# Wafer_Schematic.net
KiCad netlist of a schematic drawn in Altium Designer
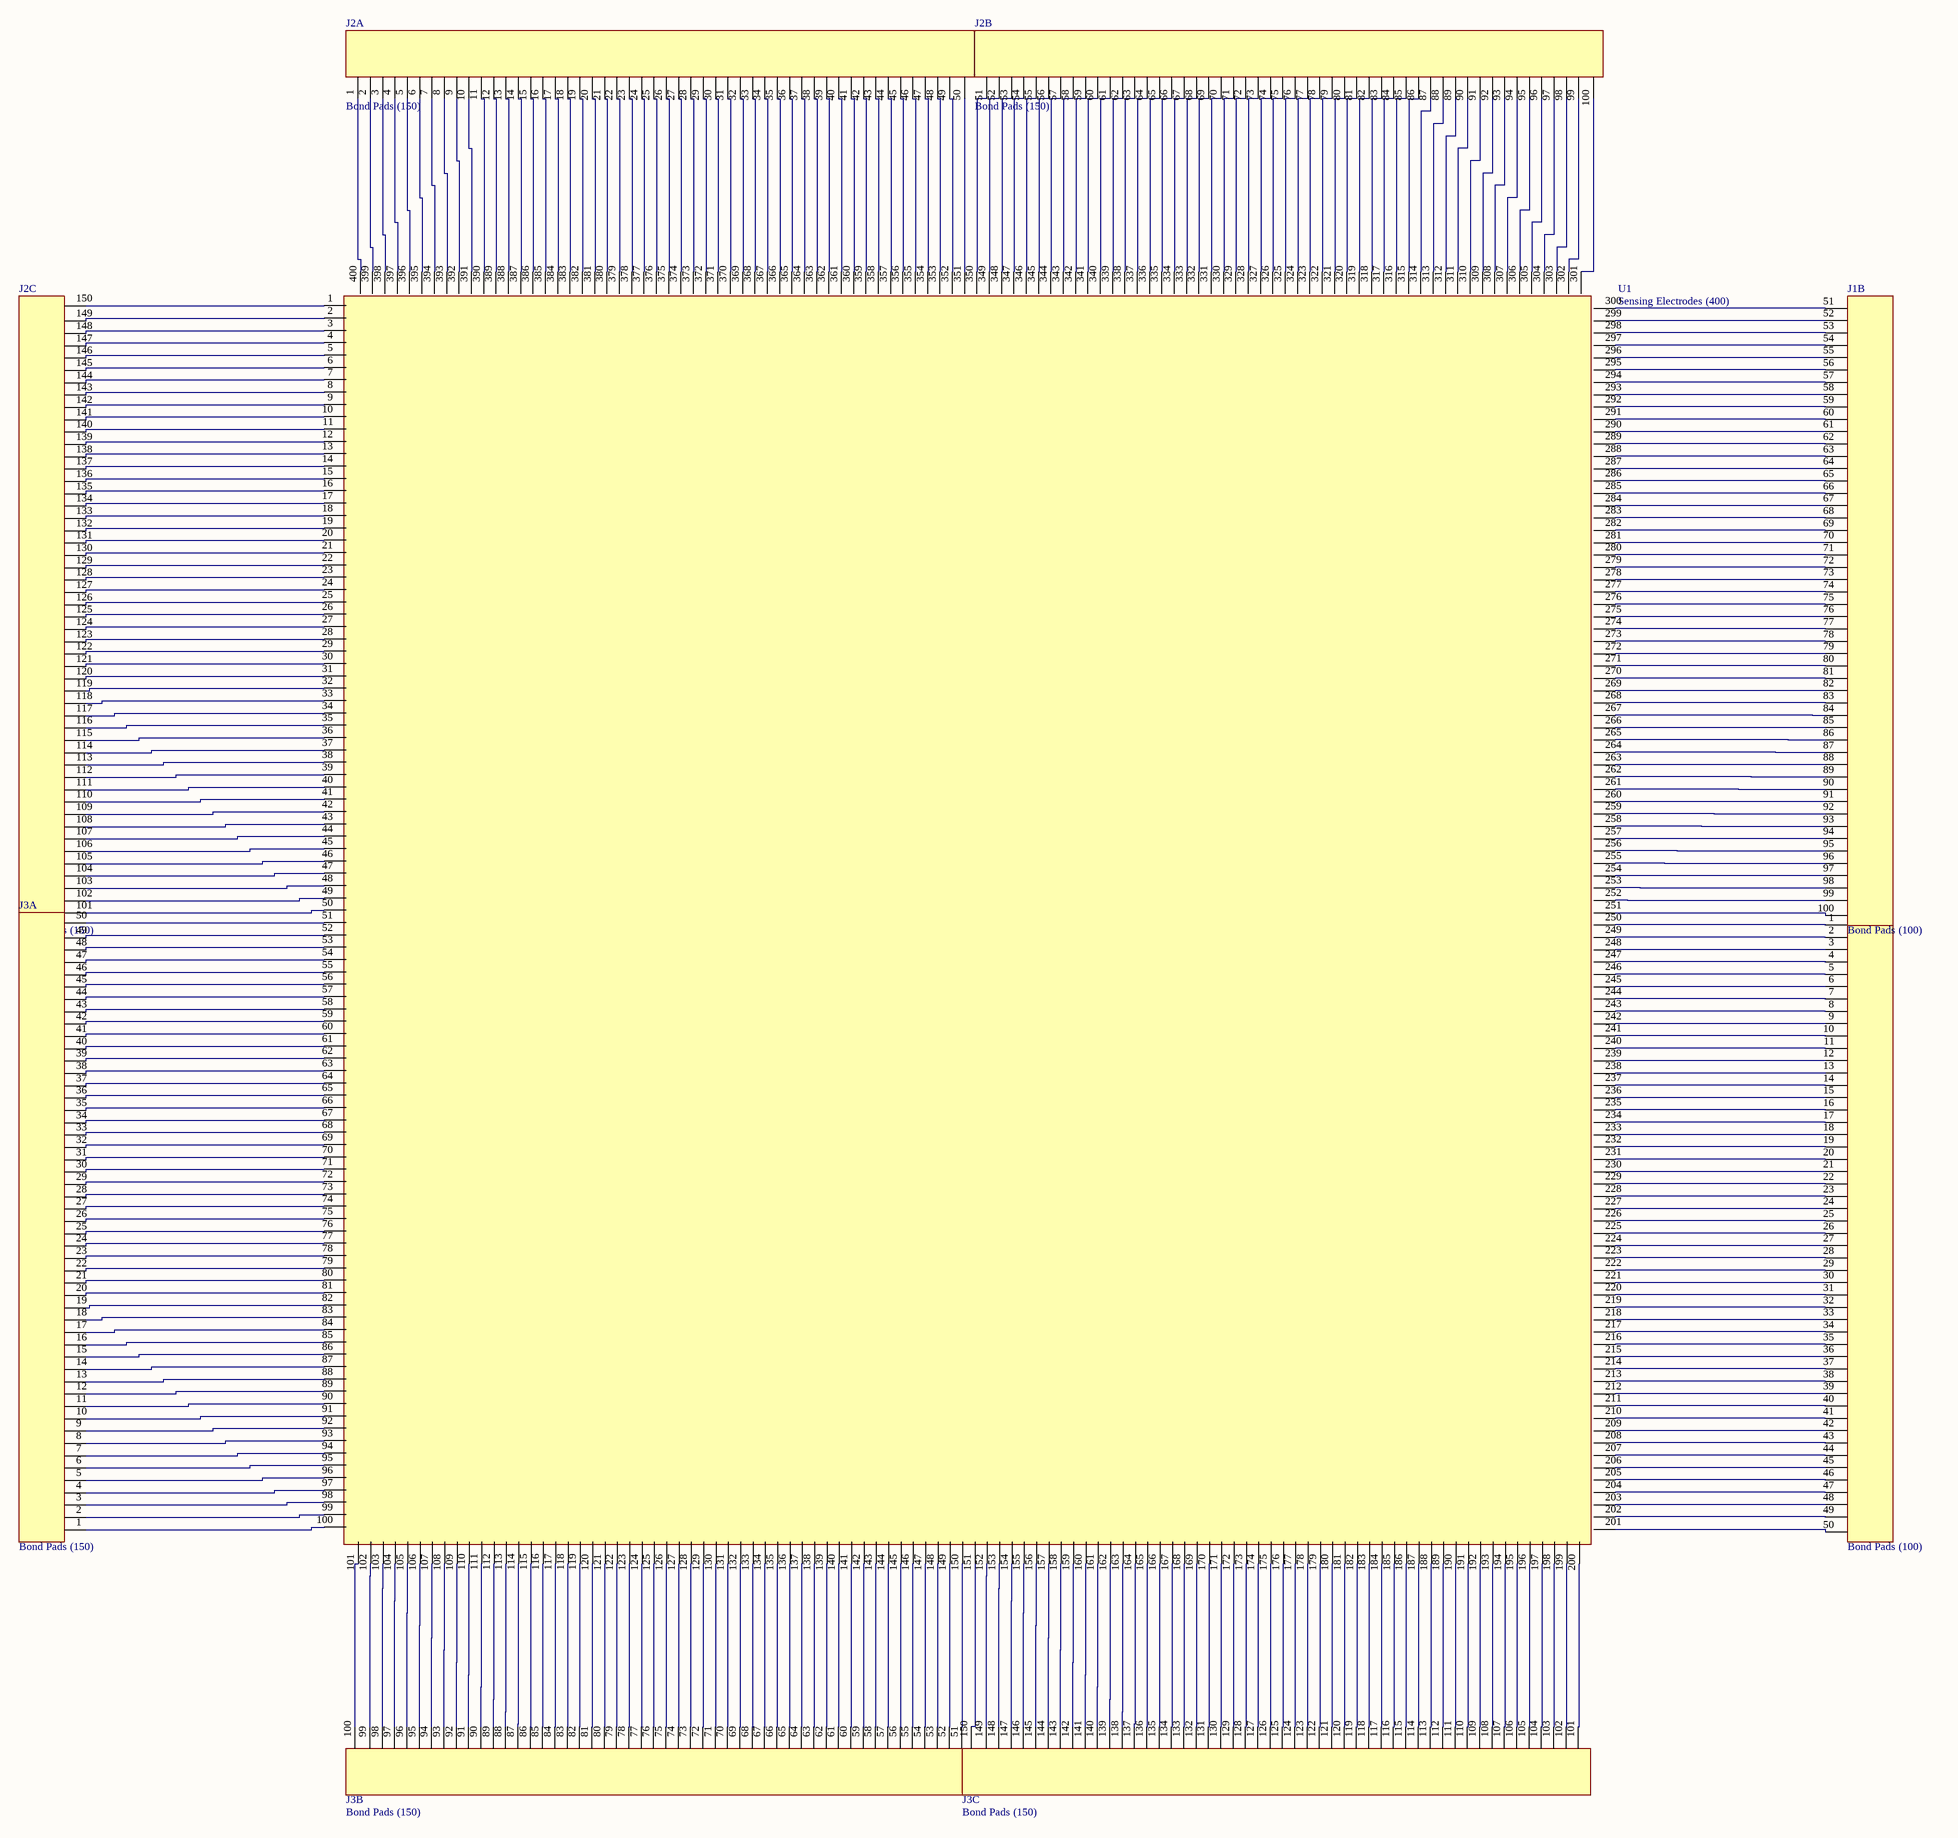
[diagram p0: Wafer Schematic.SchDoc]

(export (version "E")
  (design (tool "Eeschema 10.0.6"))
  (components
    (comp (ref "J1")
      (value "Bond Pads (100)")
      (footprint "BOND PADS (100)")
      (description "100 pads for the shorter side of the chip")
      (libsource (lib "Celestial Library Database") (part "Bond Pads (100)"))
    )
    (comp (ref "J2")
      (value "Bond Pads (150)")
      (footprint "BOND PADS (150)")
      (description "150 pads for the longer side of the chip")
      (libsource (lib "") (part "Bond Pads (150)_1"))
    )
    (comp (ref "J3")
      (value "Bond Pads (150)")
      (footprint "BOND PADS (150)")
      (description "150 pads for the longer side of the chip")
      (libsource (lib "Celestial Library Database") (part "Bond Pads (150)"))
    )
    (comp (ref "U1")
      (value "Sensing Electrodes (400)")
      (footprint "LGA400C100P20X20_2000X2000X0")
      (description "400 Electrodes covering a 2 mm by 2 mm sensing 10x")
      (fields (field (name "PART NUMBER") "Silicon Die Holder 400 Electrodes"))
      (libsource (lib "Celestial Library Database") (part "Sensing Electrodes (400)"))
    )
  )
  (nets
    (net (code "1") (name "Net-(J1-Pad1)") (class "Default")
      (node (ref "J1") (pin "1") (pintype "passive"))
      (node (ref "U1") (pin "250") (pintype "passive"))
    )
    (net (code "2") (name "Net-(J1-Pad2)") (class "Default")
      (node (ref "J1") (pin "2") (pintype "passive"))
      (node (ref "U1") (pin "249") (pintype "passive"))
    )
    (net (code "3") (name "Net-(J1-Pad3)") (class "Default")
      (node (ref "J1") (pin "3") (pintype "passive"))
      (node (ref "U1") (pin "248") (pintype "passive"))
    )
    (net (code "4") (name "Net-(J1-Pad4)") (class "Default")
      (node (ref "J1") (pin "4") (pintype "passive"))
      (node (ref "U1") (pin "247") (pintype "passive"))
    )
    (net (code "5") (name "Net-(J1-Pad5)") (class "Default")
      (node (ref "J1") (pin "5") (pintype "passive"))
      (node (ref "U1") (pin "246") (pintype "passive"))
    )
    (net (code "6") (name "Net-(J1-Pad6)") (class "Default")
      (node (ref "J1") (pin "6") (pintype "passive"))
      (node (ref "U1") (pin "245") (pintype "passive"))
    )
    (net (code "7") (name "Net-(J1-Pad7)") (class "Default")
      (node (ref "J1") (pin "7") (pintype "passive"))
      (node (ref "U1") (pin "244") (pintype "passive"))
    )
    (net (code "8") (name "Net-(J1-Pad8)") (class "Default")
      (node (ref "J1") (pin "8") (pintype "passive"))
      (node (ref "U1") (pin "243") (pintype "passive"))
    )
    (net (code "9") (name "Net-(J1-Pad9)") (class "Default")
      (node (ref "J1") (pin "9") (pintype "passive"))
      (node (ref "U1") (pin "242") (pintype "passive"))
    )
    (net (code "10") (name "Net-(J1-Pad10)") (class "Default")
      (node (ref "J1") (pin "10") (pintype "passive"))
      (node (ref "U1") (pin "241") (pintype "passive"))
    )
    (net (code "11") (name "Net-(J1-Pad11)") (class "Default")
      (node (ref "J1") (pin "11") (pintype "passive"))
      (node (ref "U1") (pin "240") (pintype "passive"))
    )
    (net (code "12") (name "Net-(J1-Pad12)") (class "Default")
      (node (ref "J1") (pin "12") (pintype "passive"))
      (node (ref "U1") (pin "239") (pintype "passive"))
    )
    (net (code "13") (name "Net-(J1-Pad13)") (class "Default")
      (node (ref "J1") (pin "13") (pintype "passive"))
      (node (ref "U1") (pin "238") (pintype "passive"))
    )
    (net (code "14") (name "Net-(J1-Pad14)") (class "Default")
      (node (ref "J1") (pin "14") (pintype "passive"))
      (node (ref "U1") (pin "237") (pintype "passive"))
    )
    (net (code "15") (name "Net-(J1-Pad15)") (class "Default")
      (node (ref "J1") (pin "15") (pintype "passive"))
      (node (ref "U1") (pin "236") (pintype "passive"))
    )
    (net (code "16") (name "Net-(J1-Pad16)") (class "Default")
      (node (ref "J1") (pin "16") (pintype "passive"))
      (node (ref "U1") (pin "235") (pintype "passive"))
    )
    (net (code "17") (name "Net-(J1-Pad17)") (class "Default")
      (node (ref "J1") (pin "17") (pintype "passive"))
      (node (ref "U1") (pin "234") (pintype "passive"))
    )
    (net (code "18") (name "Net-(J1-Pad18)") (class "Default")
      (node (ref "J1") (pin "18") (pintype "passive"))
      (node (ref "U1") (pin "233") (pintype "passive"))
    )
    (net (code "19") (name "Net-(J1-Pad19)") (class "Default")
      (node (ref "J1") (pin "19") (pintype "passive"))
      (node (ref "U1") (pin "232") (pintype "passive"))
    )
    (net (code "20") (name "Net-(J1-Pad20)") (class "Default")
      (node (ref "J1") (pin "20") (pintype "passive"))
      (node (ref "U1") (pin "231") (pintype "passive"))
    )
    (net (code "21") (name "Net-(J1-Pad21)") (class "Default")
      (node (ref "J1") (pin "21") (pintype "passive"))
      (node (ref "U1") (pin "230") (pintype "passive"))
    )
    (net (code "22") (name "Net-(J1-Pad22)") (class "Default")
      (node (ref "J1") (pin "22") (pintype "passive"))
      (node (ref "U1") (pin "229") (pintype "passive"))
    )
    (net (code "23") (name "Net-(J1-Pad23)") (class "Default")
      (node (ref "J1") (pin "23") (pintype "passive"))
      (node (ref "U1") (pin "228") (pintype "passive"))
    )
    (net (code "24") (name "Net-(J1-Pad24)") (class "Default")
      (node (ref "J1") (pin "24") (pintype "passive"))
      (node (ref "U1") (pin "227") (pintype "passive"))
    )
    (net (code "25") (name "Net-(J1-Pad25)") (class "Default")
      (node (ref "J1") (pin "25") (pintype "passive"))
      (node (ref "U1") (pin "226") (pintype "passive"))
    )
    (net (code "26") (name "Net-(J1-Pad26)") (class "Default")
      (node (ref "J1") (pin "26") (pintype "passive"))
      (node (ref "U1") (pin "225") (pintype "passive"))
    )
    (net (code "27") (name "Net-(J1-Pad27)") (class "Default")
      (node (ref "J1") (pin "27") (pintype "passive"))
      (node (ref "U1") (pin "224") (pintype "passive"))
    )
    (net (code "28") (name "Net-(J1-Pad28)") (class "Default")
      (node (ref "J1") (pin "28") (pintype "passive"))
      (node (ref "U1") (pin "223") (pintype "passive"))
    )
    (net (code "29") (name "Net-(J1-Pad29)") (class "Default")
      (node (ref "J1") (pin "29") (pintype "passive"))
      (node (ref "U1") (pin "222") (pintype "passive"))
    )
    (net (code "30") (name "Net-(J1-Pad30)") (class "Default")
      (node (ref "J1") (pin "30") (pintype "passive"))
      (node (ref "U1") (pin "221") (pintype "passive"))
    )
    (net (code "31") (name "Net-(J1-Pad31)") (class "Default")
      (node (ref "J1") (pin "31") (pintype "passive"))
      (node (ref "U1") (pin "220") (pintype "passive"))
    )
    (net (code "32") (name "Net-(J1-Pad32)") (class "Default")
      (node (ref "J1") (pin "32") (pintype "passive"))
      (node (ref "U1") (pin "219") (pintype "passive"))
    )
    (net (code "33") (name "Net-(J1-Pad33)") (class "Default")
      (node (ref "J1") (pin "33") (pintype "passive"))
      (node (ref "U1") (pin "218") (pintype "passive"))
    )
    (net (code "34") (name "Net-(J1-Pad34)") (class "Default")
      (node (ref "J1") (pin "34") (pintype "passive"))
      (node (ref "U1") (pin "217") (pintype "passive"))
    )
    (net (code "35") (name "Net-(J1-Pad35)") (class "Default")
      (node (ref "J1") (pin "35") (pintype "passive"))
      (node (ref "U1") (pin "216") (pintype "passive"))
    )
    (net (code "36") (name "Net-(J1-Pad36)") (class "Default")
      (node (ref "J1") (pin "36") (pintype "passive"))
      (node (ref "U1") (pin "215") (pintype "passive"))
    )
    (net (code "37") (name "Net-(J1-Pad37)") (class "Default")
      (node (ref "J1") (pin "37") (pintype "passive"))
      (node (ref "U1") (pin "214") (pintype "passive"))
    )
    (net (code "38") (name "Net-(J1-Pad38)") (class "Default")
      (node (ref "J1") (pin "38") (pintype "passive"))
      (node (ref "U1") (pin "213") (pintype "passive"))
    )
    (net (code "39") (name "Net-(J1-Pad39)") (class "Default")
      (node (ref "J1") (pin "39") (pintype "passive"))
      (node (ref "U1") (pin "212") (pintype "passive"))
    )
    (net (code "40") (name "Net-(J1-Pad40)") (class "Default")
      (node (ref "J1") (pin "40") (pintype "passive"))
      (node (ref "U1") (pin "211") (pintype "passive"))
    )
    (net (code "41") (name "Net-(J1-Pad41)") (class "Default")
      (node (ref "J1") (pin "41") (pintype "passive"))
      (node (ref "U1") (pin "210") (pintype "passive"))
    )
    (net (code "42") (name "Net-(J1-Pad42)") (class "Default")
      (node (ref "J1") (pin "42") (pintype "passive"))
      (node (ref "U1") (pin "209") (pintype "passive"))
    )
    (net (code "43") (name "Net-(J1-Pad43)") (class "Default")
      (node (ref "J1") (pin "43") (pintype "passive"))
      (node (ref "U1") (pin "208") (pintype "passive"))
    )
    (net (code "44") (name "Net-(J1-Pad44)") (class "Default")
      (node (ref "J1") (pin "44") (pintype "passive"))
      (node (ref "U1") (pin "207") (pintype "passive"))
    )
    (net (code "45") (name "Net-(J1-Pad45)") (class "Default")
      (node (ref "J1") (pin "45") (pintype "passive"))
      (node (ref "U1") (pin "206") (pintype "passive"))
    )
    (net (code "46") (name "Net-(J1-Pad46)") (class "Default")
      (node (ref "J1") (pin "46") (pintype "passive"))
      (node (ref "U1") (pin "205") (pintype "passive"))
    )
    (net (code "47") (name "Net-(J1-Pad47)") (class "Default")
      (node (ref "J1") (pin "47") (pintype "passive"))
      (node (ref "U1") (pin "204") (pintype "passive"))
    )
    (net (code "48") (name "Net-(J1-Pad48)") (class "Default")
      (node (ref "J1") (pin "48") (pintype "passive"))
      (node (ref "U1") (pin "203") (pintype "passive"))
    )
    (net (code "49") (name "Net-(J1-Pad49)") (class "Default")
      (node (ref "J1") (pin "49") (pintype "passive"))
      (node (ref "U1") (pin "202") (pintype "passive"))
    )
    (net (code "50") (name "Net-(J1-Pad50)") (class "Default")
      (node (ref "J1") (pin "50") (pintype "passive"))
      (node (ref "U1") (pin "201") (pintype "passive"))
    )
    (net (code "51") (name "Net-(J1-Pad51)") (class "Default")
      (node (ref "J1") (pin "51") (pintype "passive"))
      (node (ref "U1") (pin "300") (pintype "passive"))
    )
    (net (code "52") (name "Net-(J1-Pad52)") (class "Default")
      (node (ref "J1") (pin "52") (pintype "passive"))
      (node (ref "U1") (pin "299") (pintype "passive"))
    )
    (net (code "53") (name "Net-(J1-Pad53)") (class "Default")
      (node (ref "J1") (pin "53") (pintype "passive"))
      (node (ref "U1") (pin "298") (pintype "passive"))
    )
    (net (code "54") (name "Net-(J1-Pad54)") (class "Default")
      (node (ref "J1") (pin "54") (pintype "passive"))
      (node (ref "U1") (pin "297") (pintype "passive"))
    )
    (net (code "55") (name "Net-(J1-Pad55)") (class "Default")
      (node (ref "J1") (pin "55") (pintype "passive"))
      (node (ref "U1") (pin "296") (pintype "passive"))
    )
    (net (code "56") (name "Net-(J1-Pad56)") (class "Default")
      (node (ref "J1") (pin "56") (pintype "passive"))
      (node (ref "U1") (pin "295") (pintype "passive"))
    )
    (net (code "57") (name "Net-(J1-Pad57)") (class "Default")
      (node (ref "J1") (pin "57") (pintype "passive"))
      (node (ref "U1") (pin "294") (pintype "passive"))
    )
    (net (code "58") (name "Net-(J1-Pad58)") (class "Default")
      (node (ref "J1") (pin "58") (pintype "passive"))
      (node (ref "U1") (pin "293") (pintype "passive"))
    )
    (net (code "59") (name "Net-(J1-Pad59)") (class "Default")
      (node (ref "J1") (pin "59") (pintype "passive"))
      (node (ref "U1") (pin "292") (pintype "passive"))
    )
    (net (code "60") (name "Net-(J1-Pad60)") (class "Default")
      (node (ref "J1") (pin "60") (pintype "passive"))
      (node (ref "U1") (pin "291") (pintype "passive"))
    )
    (net (code "61") (name "Net-(J1-Pad61)") (class "Default")
      (node (ref "J1") (pin "61") (pintype "passive"))
      (node (ref "U1") (pin "290") (pintype "passive"))
    )
    (net (code "62") (name "Net-(J1-Pad62)") (class "Default")
      (node (ref "J1") (pin "62") (pintype "passive"))
      (node (ref "U1") (pin "289") (pintype "passive"))
    )
    (net (code "63") (name "Net-(J1-Pad63)") (class "Default")
      (node (ref "J1") (pin "63") (pintype "passive"))
      (node (ref "U1") (pin "288") (pintype "passive"))
    )
    (net (code "64") (name "Net-(J1-Pad64)") (class "Default")
      (node (ref "J1") (pin "64") (pintype "passive"))
      (node (ref "U1") (pin "287") (pintype "passive"))
    )
    (net (code "65") (name "Net-(J1-Pad65)") (class "Default")
      (node (ref "J1") (pin "65") (pintype "passive"))
      (node (ref "U1") (pin "286") (pintype "passive"))
    )
    (net (code "66") (name "Net-(J1-Pad66)") (class "Default")
      (node (ref "J1") (pin "66") (pintype "passive"))
      (node (ref "U1") (pin "285") (pintype "passive"))
    )
    (net (code "67") (name "Net-(J1-Pad67)") (class "Default")
      (node (ref "J1") (pin "67") (pintype "passive"))
      (node (ref "U1") (pin "284") (pintype "passive"))
    )
    (net (code "68") (name "Net-(J1-Pad68)") (class "Default")
      (node (ref "J1") (pin "68") (pintype "passive"))
      (node (ref "U1") (pin "283") (pintype "passive"))
    )
    (net (code "69") (name "Net-(J1-Pad69)") (class "Default")
      (node (ref "J1") (pin "69") (pintype "passive"))
      (node (ref "U1") (pin "282") (pintype "passive"))
    )
    (net (code "70") (name "Net-(J1-Pad70)") (class "Default")
      (node (ref "J1") (pin "70") (pintype "passive"))
      (node (ref "U1") (pin "281") (pintype "passive"))
    )
    (net (code "71") (name "Net-(J1-Pad71)") (class "Default")
      (node (ref "J1") (pin "71") (pintype "passive"))
      (node (ref "U1") (pin "280") (pintype "passive"))
    )
    (net (code "72") (name "Net-(J1-Pad72)") (class "Default")
      (node (ref "J1") (pin "72") (pintype "passive"))
      (node (ref "U1") (pin "279") (pintype "passive"))
    )
    (net (code "73") (name "Net-(J1-Pad73)") (class "Default")
      (node (ref "J1") (pin "73") (pintype "passive"))
      (node (ref "U1") (pin "278") (pintype "passive"))
    )
    (net (code "74") (name "Net-(J1-Pad74)") (class "Default")
      (node (ref "J1") (pin "74") (pintype "passive"))
      (node (ref "U1") (pin "277") (pintype "passive"))
    )
    (net (code "75") (name "Net-(J1-Pad75)") (class "Default")
      (node (ref "J1") (pin "75") (pintype "passive"))
      (node (ref "U1") (pin "276") (pintype "passive"))
    )
    (net (code "76") (name "Net-(J1-Pad76)") (class "Default")
      (node (ref "J1") (pin "76") (pintype "passive"))
      (node (ref "U1") (pin "275") (pintype "passive"))
    )
    (net (code "77") (name "Net-(J1-Pad77)") (class "Default")
      (node (ref "J1") (pin "77") (pintype "passive"))
      (node (ref "U1") (pin "274") (pintype "passive"))
    )
    (net (code "78") (name "Net-(J1-Pad78)") (class "Default")
      (node (ref "J1") (pin "78") (pintype "passive"))
      (node (ref "U1") (pin "273") (pintype "passive"))
    )
    (net (code "79") (name "Net-(J1-Pad79)") (class "Default")
      (node (ref "J1") (pin "79") (pintype "passive"))
      (node (ref "U1") (pin "272") (pintype "passive"))
    )
    (net (code "80") (name "Net-(J1-Pad80)") (class "Default")
      (node (ref "J1") (pin "80") (pintype "passive"))
      (node (ref "U1") (pin "271") (pintype "passive"))
    )
    (net (code "81") (name "Net-(J1-Pad81)") (class "Default")
      (node (ref "J1") (pin "81") (pintype "passive"))
      (node (ref "U1") (pin "270") (pintype "passive"))
    )
    (net (code "82") (name "Net-(J1-Pad82)") (class "Default")
      (node (ref "J1") (pin "82") (pintype "passive"))
      (node (ref "U1") (pin "269") (pintype "passive"))
    )
    (net (code "83") (name "Net-(J1-Pad83)") (class "Default")
      (node (ref "J1") (pin "83") (pintype "passive"))
      (node (ref "U1") (pin "268") (pintype "passive"))
    )
    (net (code "84") (name "Net-(J1-Pad84)") (class "Default")
      (node (ref "J1") (pin "84") (pintype "passive"))
      (node (ref "U1") (pin "267") (pintype "passive"))
    )
    (net (code "85") (name "Net-(J1-Pad85)") (class "Default")
      (node (ref "J1") (pin "85") (pintype "passive"))
      (node (ref "U1") (pin "266") (pintype "passive"))
    )
    (net (code "86") (name "Net-(J1-Pad86)") (class "Default")
      (node (ref "J1") (pin "86") (pintype "passive"))
      (node (ref "U1") (pin "265") (pintype "passive"))
    )
    (net (code "87") (name "Net-(J1-Pad87)") (class "Default")
      (node (ref "J1") (pin "87") (pintype "passive"))
      (node (ref "U1") (pin "264") (pintype "passive"))
    )
    (net (code "88") (name "Net-(J1-Pad88)") (class "Default")
      (node (ref "J1") (pin "88") (pintype "passive"))
      (node (ref "U1") (pin "263") (pintype "passive"))
    )
    (net (code "89") (name "Net-(J1-Pad89)") (class "Default")
      (node (ref "J1") (pin "89") (pintype "passive"))
      (node (ref "U1") (pin "262") (pintype "passive"))
    )
    (net (code "90") (name "Net-(J1-Pad90)") (class "Default")
      (node (ref "J1") (pin "90") (pintype "passive"))
      (node (ref "U1") (pin "261") (pintype "passive"))
    )
    (net (code "91") (name "Net-(J1-Pad91)") (class "Default")
      (node (ref "J1") (pin "91") (pintype "passive"))
      (node (ref "U1") (pin "260") (pintype "passive"))
    )
    (net (code "92") (name "Net-(J1-Pad92)") (class "Default")
      (node (ref "J1") (pin "92") (pintype "passive"))
      (node (ref "U1") (pin "259") (pintype "passive"))
    )
    (net (code "93") (name "Net-(J1-Pad93)") (class "Default")
      (node (ref "J1") (pin "93") (pintype "passive"))
      (node (ref "U1") (pin "258") (pintype "passive"))
    )
    (net (code "94") (name "Net-(J1-Pad94)") (class "Default")
      (node (ref "J1") (pin "94") (pintype "passive"))
      (node (ref "U1") (pin "257") (pintype "passive"))
    )
    (net (code "95") (name "Net-(J1-Pad95)") (class "Default")
      (node (ref "J1") (pin "95") (pintype "passive"))
      (node (ref "U1") (pin "256") (pintype "passive"))
    )
    (net (code "96") (name "Net-(J1-Pad96)") (class "Default")
      (node (ref "J1") (pin "96") (pintype "passive"))
      (node (ref "U1") (pin "255") (pintype "passive"))
    )
    (net (code "97") (name "Net-(J1-Pad97)") (class "Default")
      (node (ref "J1") (pin "97") (pintype "passive"))
      (node (ref "U1") (pin "254") (pintype "passive"))
    )
    (net (code "98") (name "Net-(J1-Pad98)") (class "Default")
      (node (ref "J1") (pin "98") (pintype "passive"))
      (node (ref "U1") (pin "253") (pintype "passive"))
    )
    (net (code "99") (name "Net-(J1-Pad99)") (class "Default")
      (node (ref "J1") (pin "99") (pintype "passive"))
      (node (ref "U1") (pin "252") (pintype "passive"))
    )
    (net (code "100") (name "Net-(J1-Pad100)") (class "Default")
      (node (ref "J1") (pin "100") (pintype "passive"))
      (node (ref "U1") (pin "251") (pintype "passive"))
    )
    (net (code "101") (name "Net-(J2-Pad1)") (class "Default")
      (node (ref "J2") (pin "1") (pintype "passive"))
      (node (ref "U1") (pin "400") (pintype "passive"))
    )
    (net (code "102") (name "Net-(J2-Pad2)") (class "Default")
      (node (ref "J2") (pin "2") (pintype "passive"))
      (node (ref "U1") (pin "399") (pintype "passive"))
    )
    (net (code "103") (name "Net-(J2-Pad3)") (class "Default")
      (node (ref "J2") (pin "3") (pintype "passive"))
      (node (ref "U1") (pin "398") (pintype "passive"))
    )
    (net (code "104") (name "Net-(J2-Pad4)") (class "Default")
      (node (ref "J2") (pin "4") (pintype "passive"))
      (node (ref "U1") (pin "397") (pintype "passive"))
    )
    (net (code "105") (name "Net-(J2-Pad5)") (class "Default")
      (node (ref "J2") (pin "5") (pintype "passive"))
      (node (ref "U1") (pin "396") (pintype "passive"))
    )
    (net (code "106") (name "Net-(J2-Pad6)") (class "Default")
      (node (ref "J2") (pin "6") (pintype "passive"))
      (node (ref "U1") (pin "395") (pintype "passive"))
    )
    (net (code "107") (name "Net-(J2-Pad7)") (class "Default")
      (node (ref "J2") (pin "7") (pintype "passive"))
      (node (ref "U1") (pin "394") (pintype "passive"))
    )
    (net (code "108") (name "Net-(J2-Pad8)") (class "Default")
      (node (ref "J2") (pin "8") (pintype "passive"))
      (node (ref "U1") (pin "393") (pintype "passive"))
    )
    (net (code "109") (name "Net-(J2-Pad9)") (class "Default")
      (node (ref "J2") (pin "9") (pintype "passive"))
      (node (ref "U1") (pin "392") (pintype "passive"))
    )
    (net (code "110") (name "Net-(J2-Pad10)") (class "Default")
      (node (ref "J2") (pin "10") (pintype "passive"))
      (node (ref "U1") (pin "391") (pintype "passive"))
    )
    (net (code "111") (name "Net-(J2-Pad11)") (class "Default")
      (node (ref "J2") (pin "11") (pintype "passive"))
      (node (ref "U1") (pin "390") (pintype "passive"))
    )
    (net (code "112") (name "Net-(J2-Pad12)") (class "Default")
      (node (ref "J2") (pin "12") (pintype "passive"))
      (node (ref "U1") (pin "389") (pintype "passive"))
    )
    (net (code "113") (name "Net-(J2-Pad13)") (class "Default")
      (node (ref "J2") (pin "13") (pintype "passive"))
      (node (ref "U1") (pin "388") (pintype "passive"))
    )
    (net (code "114") (name "Net-(J2-Pad14)") (class "Default")
      (node (ref "J2") (pin "14") (pintype "passive"))
      (node (ref "U1") (pin "387") (pintype "passive"))
    )
    (net (code "115") (name "Net-(J2-Pad15)") (class "Default")
      (node (ref "J2") (pin "15") (pintype "passive"))
      (node (ref "U1") (pin "386") (pintype "passive"))
    )
    (net (code "116") (name "Net-(J2-Pad16)") (class "Default")
      (node (ref "J2") (pin "16") (pintype "passive"))
      (node (ref "U1") (pin "385") (pintype "passive"))
    )
    (net (code "117") (name "Net-(J2-Pad17)") (class "Default")
      (node (ref "J2") (pin "17") (pintype "passive"))
      (node (ref "U1") (pin "384") (pintype "passive"))
    )
    (net (code "118") (name "Net-(J2-Pad18)") (class "Default")
      (node (ref "J2") (pin "18") (pintype "passive"))
      (node (ref "U1") (pin "383") (pintype "passive"))
    )
    (net (code "119") (name "Net-(J2-Pad19)") (class "Default")
      (node (ref "J2") (pin "19") (pintype "passive"))
      (node (ref "U1") (pin "382") (pintype "passive"))
    )
    (net (code "120") (name "Net-(J2-Pad20)") (class "Default")
      (node (ref "J2") (pin "20") (pintype "passive"))
      (node (ref "U1") (pin "381") (pintype "passive"))
    )
    (net (code "121") (name "Net-(J2-Pad21)") (class "Default")
      (node (ref "J2") (pin "21") (pintype "passive"))
      (node (ref "U1") (pin "380") (pintype "passive"))
    )
    (net (code "122") (name "Net-(J2-Pad22)") (class "Default")
      (node (ref "J2") (pin "22") (pintype "passive"))
      (node (ref "U1") (pin "379") (pintype "passive"))
    )
    (net (code "123") (name "Net-(J2-Pad23)") (class "Default")
      (node (ref "J2") (pin "23") (pintype "passive"))
      (node (ref "U1") (pin "378") (pintype "passive"))
    )
    (net (code "124") (name "Net-(J2-Pad24)") (class "Default")
      (node (ref "J2") (pin "24") (pintype "passive"))
      (node (ref "U1") (pin "377") (pintype "passive"))
    )
    (net (code "125") (name "Net-(J2-Pad25)") (class "Default")
      (node (ref "J2") (pin "25") (pintype "passive"))
      (node (ref "U1") (pin "376") (pintype "passive"))
    )
    (net (code "126") (name "Net-(J2-Pad26)") (class "Default")
      (node (ref "J2") (pin "26") (pintype "passive"))
      (node (ref "U1") (pin "375") (pintype "passive"))
    )
    (net (code "127") (name "Net-(J2-Pad27)") (class "Default")
      (node (ref "J2") (pin "27") (pintype "passive"))
      (node (ref "U1") (pin "374") (pintype "passive"))
    )
    (net (code "128") (name "Net-(J2-Pad28)") (class "Default")
      (node (ref "J2") (pin "28") (pintype "passive"))
      (node (ref "U1") (pin "373") (pintype "passive"))
    )
    (net (code "129") (name "Net-(J2-Pad29)") (class "Default")
      (node (ref "J2") (pin "29") (pintype "passive"))
      (node (ref "U1") (pin "372") (pintype "passive"))
    )
    (net (code "130") (name "Net-(J2-Pad30)") (class "Default")
      (node (ref "J2") (pin "30") (pintype "passive"))
      (node (ref "U1") (pin "371") (pintype "passive"))
    )
    (net (code "131") (name "Net-(J2-Pad31)") (class "Default")
      (node (ref "J2") (pin "31") (pintype "passive"))
      (node (ref "U1") (pin "370") (pintype "passive"))
    )
    (net (code "132") (name "Net-(J2-Pad32)") (class "Default")
      (node (ref "J2") (pin "32") (pintype "passive"))
      (node (ref "U1") (pin "369") (pintype "passive"))
    )
    (net (code "133") (name "Net-(J2-Pad33)") (class "Default")
      (node (ref "J2") (pin "33") (pintype "passive"))
      (node (ref "U1") (pin "368") (pintype "passive"))
    )
    (net (code "134") (name "Net-(J2-Pad34)") (class "Default")
      (node (ref "J2") (pin "34") (pintype "passive"))
      (node (ref "U1") (pin "367") (pintype "passive"))
    )
    (net (code "135") (name "Net-(J2-Pad35)") (class "Default")
      (node (ref "J2") (pin "35") (pintype "passive"))
      (node (ref "U1") (pin "366") (pintype "passive"))
    )
    (net (code "136") (name "Net-(J2-Pad36)") (class "Default")
      (node (ref "J2") (pin "36") (pintype "passive"))
      (node (ref "U1") (pin "365") (pintype "passive"))
    )
    (net (code "137") (name "Net-(J2-Pad37)") (class "Default")
      (node (ref "J2") (pin "37") (pintype "passive"))
      (node (ref "U1") (pin "364") (pintype "passive"))
    )
    (net (code "138") (name "Net-(J2-Pad38)") (class "Default")
      (node (ref "J2") (pin "38") (pintype "passive"))
      (node (ref "U1") (pin "363") (pintype "passive"))
    )
    (net (code "139") (name "Net-(J2-Pad39)") (class "Default")
      (node (ref "J2") (pin "39") (pintype "passive"))
      (node (ref "U1") (pin "362") (pintype "passive"))
    )
    (net (code "140") (name "Net-(J2-Pad40)") (class "Default")
      (node (ref "J2") (pin "40") (pintype "passive"))
      (node (ref "U1") (pin "361") (pintype "passive"))
    )
    (net (code "141") (name "Net-(J2-Pad41)") (class "Default")
      (node (ref "J2") (pin "41") (pintype "passive"))
      (node (ref "U1") (pin "360") (pintype "passive"))
    )
    (net (code "142") (name "Net-(J2-Pad42)") (class "Default")
      (node (ref "J2") (pin "42") (pintype "passive"))
      (node (ref "U1") (pin "359") (pintype "passive"))
    )
    (net (code "143") (name "Net-(J2-Pad43)") (class "Default")
      (node (ref "J2") (pin "43") (pintype "passive"))
      (node (ref "U1") (pin "358") (pintype "passive"))
    )
    (net (code "144") (name "Net-(J2-Pad44)") (class "Default")
      (node (ref "J2") (pin "44") (pintype "passive"))
      (node (ref "U1") (pin "357") (pintype "passive"))
    )
    (net (code "145") (name "Net-(J2-Pad45)") (class "Default")
      (node (ref "J2") (pin "45") (pintype "passive"))
      (node (ref "U1") (pin "356") (pintype "passive"))
    )
    (net (code "146") (name "Net-(J2-Pad46)") (class "Default")
      (node (ref "J2") (pin "46") (pintype "passive"))
      (node (ref "U1") (pin "355") (pintype "passive"))
    )
    (net (code "147") (name "Net-(J2-Pad47)") (class "Default")
      (node (ref "J2") (pin "47") (pintype "passive"))
      (node (ref "U1") (pin "354") (pintype "passive"))
    )
    (net (code "148") (name "Net-(J2-Pad48)") (class "Default")
      (node (ref "J2") (pin "48") (pintype "passive"))
      (node (ref "U1") (pin "353") (pintype "passive"))
    )
    (net (code "149") (name "Net-(J2-Pad49)") (class "Default")
      (node (ref "J2") (pin "49") (pintype "passive"))
      (node (ref "U1") (pin "352") (pintype "passive"))
    )
    (net (code "150") (name "Net-(J2-Pad50)") (class "Default")
      (node (ref "J2") (pin "50") (pintype "passive"))
      (node (ref "U1") (pin "351") (pintype "passive"))
    )
    (net (code "151") (name "Net-(J2-Pad51)") (class "Default")
      (node (ref "J2") (pin "51") (pintype "passive"))
      (node (ref "U1") (pin "350") (pintype "passive"))
    )
    (net (code "152") (name "Net-(J2-Pad52)") (class "Default")
      (node (ref "J2") (pin "52") (pintype "passive"))
      (node (ref "U1") (pin "349") (pintype "passive"))
    )
    (net (code "153") (name "Net-(J2-Pad53)") (class "Default")
      (node (ref "J2") (pin "53") (pintype "passive"))
      (node (ref "U1") (pin "348") (pintype "passive"))
    )
    (net (code "154") (name "Net-(J2-Pad54)") (class "Default")
      (node (ref "J2") (pin "54") (pintype "passive"))
      (node (ref "U1") (pin "347") (pintype "passive"))
    )
    (net (code "155") (name "Net-(J2-Pad55)") (class "Default")
      (node (ref "J2") (pin "55") (pintype "passive"))
      (node (ref "U1") (pin "346") (pintype "passive"))
    )
    (net (code "156") (name "Net-(J2-Pad56)") (class "Default")
      (node (ref "J2") (pin "56") (pintype "passive"))
      (node (ref "U1") (pin "345") (pintype "passive"))
    )
    (net (code "157") (name "Net-(J2-Pad57)") (class "Default")
      (node (ref "J2") (pin "57") (pintype "passive"))
      (node (ref "U1") (pin "344") (pintype "passive"))
    )
    (net (code "158") (name "Net-(J2-Pad58)") (class "Default")
      (node (ref "J2") (pin "58") (pintype "passive"))
      (node (ref "U1") (pin "343") (pintype "passive"))
    )
    (net (code "159") (name "Net-(J2-Pad59)") (class "Default")
      (node (ref "J2") (pin "59") (pintype "passive"))
      (node (ref "U1") (pin "342") (pintype "passive"))
    )
    (net (code "160") (name "Net-(J2-Pad60)") (class "Default")
      (node (ref "J2") (pin "60") (pintype "passive"))
      (node (ref "U1") (pin "341") (pintype "passive"))
    )
    (net (code "161") (name "Net-(J2-Pad61)") (class "Default")
      (node (ref "J2") (pin "61") (pintype "passive"))
      (node (ref "U1") (pin "340") (pintype "passive"))
    )
    (net (code "162") (name "Net-(J2-Pad62)") (class "Default")
      (node (ref "J2") (pin "62") (pintype "passive"))
      (node (ref "U1") (pin "339") (pintype "passive"))
    )
    (net (code "163") (name "Net-(J2-Pad63)") (class "Default")
      (node (ref "J2") (pin "63") (pintype "passive"))
      (node (ref "U1") (pin "338") (pintype "passive"))
    )
    (net (code "164") (name "Net-(J2-Pad64)") (class "Default")
      (node (ref "J2") (pin "64") (pintype "passive"))
      (node (ref "U1") (pin "337") (pintype "passive"))
    )
    (net (code "165") (name "Net-(J2-Pad65)") (class "Default")
      (node (ref "J2") (pin "65") (pintype "passive"))
      (node (ref "U1") (pin "336") (pintype "passive"))
    )
    (net (code "166") (name "Net-(J2-Pad66)") (class "Default")
      (node (ref "J2") (pin "66") (pintype "passive"))
      (node (ref "U1") (pin "335") (pintype "passive"))
    )
    (net (code "167") (name "Net-(J2-Pad67)") (class "Default")
      (node (ref "J2") (pin "67") (pintype "passive"))
      (node (ref "U1") (pin "334") (pintype "passive"))
    )
    (net (code "168") (name "Net-(J2-Pad68)") (class "Default")
      (node (ref "J2") (pin "68") (pintype "passive"))
      (node (ref "U1") (pin "333") (pintype "passive"))
    )
    (net (code "169") (name "Net-(J2-Pad69)") (class "Default")
      (node (ref "J2") (pin "69") (pintype "passive"))
      (node (ref "U1") (pin "332") (pintype "passive"))
    )
    (net (code "170") (name "Net-(J2-Pad70)") (class "Default")
      (node (ref "J2") (pin "70") (pintype "passive"))
      (node (ref "U1") (pin "331") (pintype "passive"))
    )
    (net (code "171") (name "Net-(J2-Pad71)") (class "Default")
      (node (ref "J2") (pin "71") (pintype "passive"))
      (node (ref "U1") (pin "330") (pintype "passive"))
    )
    (net (code "172") (name "Net-(J2-Pad72)") (class "Default")
      (node (ref "J2") (pin "72") (pintype "passive"))
      (node (ref "U1") (pin "329") (pintype "passive"))
    )
    (net (code "173") (name "Net-(J2-Pad73)") (class "Default")
      (node (ref "J2") (pin "73") (pintype "passive"))
      (node (ref "U1") (pin "328") (pintype "passive"))
    )
    (net (code "174") (name "Net-(J2-Pad74)") (class "Default")
      (node (ref "J2") (pin "74") (pintype "passive"))
      (node (ref "U1") (pin "327") (pintype "passive"))
    )
    (net (code "175") (name "Net-(J2-Pad75)") (class "Default")
      (node (ref "J2") (pin "75") (pintype "passive"))
      (node (ref "U1") (pin "326") (pintype "passive"))
    )
    (net (code "176") (name "Net-(J2-Pad76)") (class "Default")
      (node (ref "J2") (pin "76") (pintype "passive"))
      (node (ref "U1") (pin "325") (pintype "passive"))
    )
    (net (code "177") (name "Net-(J2-Pad77)") (class "Default")
      (node (ref "J2") (pin "77") (pintype "passive"))
      (node (ref "U1") (pin "324") (pintype "passive"))
    )
    (net (code "178") (name "Net-(J2-Pad78)") (class "Default")
      (node (ref "J2") (pin "78") (pintype "passive"))
      (node (ref "U1") (pin "323") (pintype "passive"))
    )
    (net (code "179") (name "Net-(J2-Pad79)") (class "Default")
      (node (ref "J2") (pin "79") (pintype "passive"))
      (node (ref "U1") (pin "322") (pintype "passive"))
    )
    (net (code "180") (name "Net-(J2-Pad80)") (class "Default")
      (node (ref "J2") (pin "80") (pintype "passive"))
      (node (ref "U1") (pin "321") (pintype "passive"))
    )
    (net (code "181") (name "Net-(J2-Pad81)") (class "Default")
      (node (ref "J2") (pin "81") (pintype "passive"))
      (node (ref "U1") (pin "320") (pintype "passive"))
    )
    (net (code "182") (name "Net-(J2-Pad82)") (class "Default")
      (node (ref "J2") (pin "82") (pintype "passive"))
      (node (ref "U1") (pin "319") (pintype "passive"))
    )
    (net (code "183") (name "Net-(J2-Pad83)") (class "Default")
      (node (ref "J2") (pin "83") (pintype "passive"))
      (node (ref "U1") (pin "318") (pintype "passive"))
    )
    (net (code "184") (name "Net-(J2-Pad84)") (class "Default")
      (node (ref "J2") (pin "84") (pintype "passive"))
      (node (ref "U1") (pin "317") (pintype "passive"))
    )
    (net (code "185") (name "Net-(J2-Pad85)") (class "Default")
      (node (ref "J2") (pin "85") (pintype "passive"))
      (node (ref "U1") (pin "316") (pintype "passive"))
    )
    (net (code "186") (name "Net-(J2-Pad86)") (class "Default")
      (node (ref "J2") (pin "86") (pintype "passive"))
      (node (ref "U1") (pin "315") (pintype "passive"))
    )
    (net (code "187") (name "Net-(J2-Pad87)") (class "Default")
      (node (ref "J2") (pin "87") (pintype "passive"))
      (node (ref "U1") (pin "314") (pintype "passive"))
    )
    (net (code "188") (name "Net-(J2-Pad88)") (class "Default")
      (node (ref "J2") (pin "88") (pintype "passive"))
      (node (ref "U1") (pin "313") (pintype "passive"))
    )
    (net (code "189") (name "Net-(J2-Pad89)") (class "Default")
      (node (ref "J2") (pin "89") (pintype "passive"))
      (node (ref "U1") (pin "312") (pintype "passive"))
    )
    (net (code "190") (name "Net-(J2-Pad90)") (class "Default")
      (node (ref "J2") (pin "90") (pintype "passive"))
      (node (ref "U1") (pin "311") (pintype "passive"))
    )
    (net (code "191") (name "Net-(J2-Pad91)") (class "Default")
      (node (ref "J2") (pin "91") (pintype "passive"))
      (node (ref "U1") (pin "310") (pintype "passive"))
    )
    (net (code "192") (name "Net-(J2-Pad92)") (class "Default")
      (node (ref "J2") (pin "92") (pintype "passive"))
      (node (ref "U1") (pin "309") (pintype "passive"))
    )
    (net (code "193") (name "Net-(J2-Pad93)") (class "Default")
      (node (ref "J2") (pin "93") (pintype "passive"))
      (node (ref "U1") (pin "308") (pintype "passive"))
    )
    (net (code "194") (name "Net-(J2-Pad94)") (class "Default")
      (node (ref "J2") (pin "94") (pintype "passive"))
      (node (ref "U1") (pin "307") (pintype "passive"))
    )
    (net (code "195") (name "Net-(J2-Pad95)") (class "Default")
      (node (ref "J2") (pin "95") (pintype "passive"))
      (node (ref "U1") (pin "306") (pintype "passive"))
    )
    (net (code "196") (name "Net-(J2-Pad96)") (class "Default")
      (node (ref "J2") (pin "96") (pintype "passive"))
      (node (ref "U1") (pin "305") (pintype "passive"))
    )
    (net (code "197") (name "Net-(J2-Pad97)") (class "Default")
      (node (ref "J2") (pin "97") (pintype "passive"))
      (node (ref "U1") (pin "304") (pintype "passive"))
    )
    (net (code "198") (name "Net-(J2-Pad98)") (class "Default")
      (node (ref "J2") (pin "98") (pintype "passive"))
      (node (ref "U1") (pin "303") (pintype "passive"))
    )
    (net (code "199") (name "Net-(J2-Pad99)") (class "Default")
      (node (ref "J2") (pin "99") (pintype "passive"))
      (node (ref "U1") (pin "302") (pintype "passive"))
    )
    (net (code "200") (name "Net-(J2-Pad100)") (class "Default")
      (node (ref "J2") (pin "100") (pintype "passive"))
      (node (ref "U1") (pin "301") (pintype "passive"))
    )
    (net (code "201") (name "Net-(J2-Pad101)") (class "Default")
      (node (ref "J2") (pin "101") (pintype "passive"))
      (node (ref "U1") (pin "50") (pintype "passive"))
    )
    (net (code "202") (name "Net-(J2-Pad102)") (class "Default")
      (node (ref "J2") (pin "102") (pintype "passive"))
      (node (ref "U1") (pin "49") (pintype "passive"))
    )
    (net (code "203") (name "Net-(J2-Pad103)") (class "Default")
      (node (ref "J2") (pin "103") (pintype "passive"))
      (node (ref "U1") (pin "48") (pintype "passive"))
    )
    (net (code "204") (name "Net-(J2-Pad104)") (class "Default")
      (node (ref "J2") (pin "104") (pintype "passive"))
      (node (ref "U1") (pin "47") (pintype "passive"))
    )
    (net (code "205") (name "Net-(J2-Pad105)") (class "Default")
      (node (ref "J2") (pin "105") (pintype "passive"))
      (node (ref "U1") (pin "46") (pintype "passive"))
    )
    (net (code "206") (name "Net-(J2-Pad106)") (class "Default")
      (node (ref "J2") (pin "106") (pintype "passive"))
      (node (ref "U1") (pin "45") (pintype "passive"))
    )
    (net (code "207") (name "Net-(J2-Pad107)") (class "Default")
      (node (ref "J2") (pin "107") (pintype "passive"))
      (node (ref "U1") (pin "44") (pintype "passive"))
    )
    (net (code "208") (name "Net-(J2-Pad108)") (class "Default")
      (node (ref "J2") (pin "108") (pintype "passive"))
      (node (ref "U1") (pin "43") (pintype "passive"))
    )
    (net (code "209") (name "Net-(J2-Pad109)") (class "Default")
      (node (ref "J2") (pin "109") (pintype "passive"))
      (node (ref "U1") (pin "42") (pintype "passive"))
    )
    (net (code "210") (name "Net-(J2-Pad110)") (class "Default")
      (node (ref "J2") (pin "110") (pintype "passive"))
      (node (ref "U1") (pin "41") (pintype "passive"))
    )
    (net (code "211") (name "Net-(J2-Pad111)") (class "Default")
      (node (ref "J2") (pin "111") (pintype "passive"))
      (node (ref "U1") (pin "40") (pintype "passive"))
    )
    (net (code "212") (name "Net-(J2-Pad112)") (class "Default")
      (node (ref "J2") (pin "112") (pintype "passive"))
      (node (ref "U1") (pin "39") (pintype "passive"))
    )
    (net (code "213") (name "Net-(J2-Pad113)") (class "Default")
      (node (ref "J2") (pin "113") (pintype "passive"))
      (node (ref "U1") (pin "38") (pintype "passive"))
    )
    (net (code "214") (name "Net-(J2-Pad114)") (class "Default")
      (node (ref "J2") (pin "114") (pintype "passive"))
      (node (ref "U1") (pin "37") (pintype "passive"))
    )
    (net (code "215") (name "Net-(J2-Pad115)") (class "Default")
      (node (ref "J2") (pin "115") (pintype "passive"))
      (node (ref "U1") (pin "36") (pintype "passive"))
    )
    (net (code "216") (name "Net-(J2-Pad116)") (class "Default")
      (node (ref "J2") (pin "116") (pintype "passive"))
      (node (ref "U1") (pin "35") (pintype "passive"))
    )
    (net (code "217") (name "Net-(J2-Pad117)") (class "Default")
      (node (ref "J2") (pin "117") (pintype "passive"))
      (node (ref "U1") (pin "34") (pintype "passive"))
    )
    (net (code "218") (name "Net-(J2-Pad118)") (class "Default")
      (node (ref "J2") (pin "118") (pintype "passive"))
      (node (ref "U1") (pin "33") (pintype "passive"))
    )
    (net (code "219") (name "Net-(J2-Pad119)") (class "Default")
      (node (ref "J2") (pin "119") (pintype "passive"))
      (node (ref "U1") (pin "32") (pintype "passive"))
    )
    (net (code "220") (name "Net-(J2-Pad120)") (class "Default")
      (node (ref "J2") (pin "120") (pintype "passive"))
      (node (ref "U1") (pin "31") (pintype "passive"))
    )
    (net (code "221") (name "Net-(J2-Pad121)") (class "Default")
      (node (ref "J2") (pin "121") (pintype "passive"))
      (node (ref "U1") (pin "30") (pintype "passive"))
    )
    (net (code "222") (name "Net-(J2-Pad122)") (class "Default")
      (node (ref "J2") (pin "122") (pintype "passive"))
      (node (ref "U1") (pin "29") (pintype "passive"))
    )
    (net (code "223") (name "Net-(J2-Pad123)") (class "Default")
      (node (ref "J2") (pin "123") (pintype "passive"))
      (node (ref "U1") (pin "28") (pintype "passive"))
    )
    (net (code "224") (name "Net-(J2-Pad124)") (class "Default")
      (node (ref "J2") (pin "124") (pintype "passive"))
      (node (ref "U1") (pin "27") (pintype "passive"))
    )
    (net (code "225") (name "Net-(J2-Pad125)") (class "Default")
      (node (ref "J2") (pin "125") (pintype "passive"))
      (node (ref "U1") (pin "26") (pintype "passive"))
    )
    (net (code "226") (name "Net-(J2-Pad126)") (class "Default")
      (node (ref "J2") (pin "126") (pintype "passive"))
      (node (ref "U1") (pin "25") (pintype "passive"))
    )
    (net (code "227") (name "Net-(J2-Pad127)") (class "Default")
      (node (ref "J2") (pin "127") (pintype "passive"))
      (node (ref "U1") (pin "24") (pintype "passive"))
    )
    (net (code "228") (name "Net-(J2-Pad128)") (class "Default")
      (node (ref "J2") (pin "128") (pintype "passive"))
      (node (ref "U1") (pin "23") (pintype "passive"))
    )
    (net (code "229") (name "Net-(J2-Pad129)") (class "Default")
      (node (ref "J2") (pin "129") (pintype "passive"))
      (node (ref "U1") (pin "22") (pintype "passive"))
    )
    (net (code "230") (name "Net-(J2-Pad130)") (class "Default")
      (node (ref "J2") (pin "130") (pintype "passive"))
      (node (ref "U1") (pin "21") (pintype "passive"))
    )
    (net (code "231") (name "Net-(J2-Pad131)") (class "Default")
      (node (ref "J2") (pin "131") (pintype "passive"))
      (node (ref "U1") (pin "20") (pintype "passive"))
    )
    (net (code "232") (name "Net-(J2-Pad132)") (class "Default")
      (node (ref "J2") (pin "132") (pintype "passive"))
      (node (ref "U1") (pin "19") (pintype "passive"))
    )
    (net (code "233") (name "Net-(J2-Pad133)") (class "Default")
      (node (ref "J2") (pin "133") (pintype "passive"))
      (node (ref "U1") (pin "18") (pintype "passive"))
    )
    (net (code "234") (name "Net-(J2-Pad134)") (class "Default")
      (node (ref "J2") (pin "134") (pintype "passive"))
      (node (ref "U1") (pin "17") (pintype "passive"))
    )
    (net (code "235") (name "Net-(J2-Pad135)") (class "Default")
      (node (ref "J2") (pin "135") (pintype "passive"))
      (node (ref "U1") (pin "16") (pintype "passive"))
    )
    (net (code "236") (name "Net-(J2-Pad136)") (class "Default")
      (node (ref "J2") (pin "136") (pintype "passive"))
      (node (ref "U1") (pin "15") (pintype "passive"))
    )
    (net (code "237") (name "Net-(J2-Pad137)") (class "Default")
      (node (ref "J2") (pin "137") (pintype "passive"))
      (node (ref "U1") (pin "14") (pintype "passive"))
    )
    (net (code "238") (name "Net-(J2-Pad138)") (class "Default")
      (node (ref "J2") (pin "138") (pintype "passive"))
      (node (ref "U1") (pin "13") (pintype "passive"))
    )
    (net (code "239") (name "Net-(J2-Pad139)") (class "Default")
      (node (ref "J2") (pin "139") (pintype "passive"))
      (node (ref "U1") (pin "12") (pintype "passive"))
    )
    (net (code "240") (name "Net-(J2-Pad140)") (class "Default")
      (node (ref "J2") (pin "140") (pintype "passive"))
      (node (ref "U1") (pin "11") (pintype "passive"))
    )
    (net (code "241") (name "Net-(J2-Pad141)") (class "Default")
      (node (ref "J2") (pin "141") (pintype "passive"))
      (node (ref "U1") (pin "10") (pintype "passive"))
    )
    (net (code "242") (name "Net-(J2-Pad142)") (class "Default")
      (node (ref "J2") (pin "142") (pintype "passive"))
      (node (ref "U1") (pin "9") (pintype "passive"))
    )
    (net (code "243") (name "Net-(J2-Pad143)") (class "Default")
      (node (ref "J2") (pin "143") (pintype "passive"))
      (node (ref "U1") (pin "8") (pintype "passive"))
    )
    (net (code "244") (name "Net-(J2-Pad144)") (class "Default")
      (node (ref "J2") (pin "144") (pintype "passive"))
      (node (ref "U1") (pin "7") (pintype "passive"))
    )
    (net (code "245") (name "Net-(J2-Pad145)") (class "Default")
      (node (ref "J2") (pin "145") (pintype "passive"))
      (node (ref "U1") (pin "6") (pintype "passive"))
    )
    (net (code "246") (name "Net-(J2-Pad146)") (class "Default")
      (node (ref "J2") (pin "146") (pintype "passive"))
      (node (ref "U1") (pin "5") (pintype "passive"))
    )
    (net (code "247") (name "Net-(J2-Pad147)") (class "Default")
      (node (ref "J2") (pin "147") (pintype "passive"))
      (node (ref "U1") (pin "4") (pintype "passive"))
    )
    (net (code "248") (name "Net-(J2-Pad148)") (class "Default")
      (node (ref "J2") (pin "148") (pintype "passive"))
      (node (ref "U1") (pin "3") (pintype "passive"))
    )
    (net (code "249") (name "Net-(J2-Pad149)") (class "Default")
      (node (ref "J2") (pin "149") (pintype "passive"))
      (node (ref "U1") (pin "2") (pintype "passive"))
    )
    (net (code "250") (name "Net-(J2-Pad150)") (class "Default")
      (node (ref "J2") (pin "150") (pintype "passive"))
      (node (ref "U1") (pin "1") (pintype "passive"))
    )
    (net (code "251") (name "Net-(J3-Pad1)") (class "Default")
      (node (ref "J3") (pin "1") (pintype "passive"))
      (node (ref "U1") (pin "100") (pintype "passive"))
    )
    (net (code "252") (name "Net-(J3-Pad2)") (class "Default")
      (node (ref "J3") (pin "2") (pintype "passive"))
      (node (ref "U1") (pin "99") (pintype "passive"))
    )
    (net (code "253") (name "Net-(J3-Pad3)") (class "Default")
      (node (ref "J3") (pin "3") (pintype "passive"))
      (node (ref "U1") (pin "98") (pintype "passive"))
    )
    (net (code "254") (name "Net-(J3-Pad4)") (class "Default")
      (node (ref "J3") (pin "4") (pintype "passive"))
      (node (ref "U1") (pin "97") (pintype "passive"))
    )
    (net (code "255") (name "Net-(J3-Pad5)") (class "Default")
      (node (ref "J3") (pin "5") (pintype "passive"))
      (node (ref "U1") (pin "96") (pintype "passive"))
    )
    (net (code "256") (name "Net-(J3-Pad6)") (class "Default")
      (node (ref "J3") (pin "6") (pintype "passive"))
      (node (ref "U1") (pin "95") (pintype "passive"))
    )
    (net (code "257") (name "Net-(J3-Pad7)") (class "Default")
      (node (ref "J3") (pin "7") (pintype "passive"))
      (node (ref "U1") (pin "94") (pintype "passive"))
    )
    (net (code "258") (name "Net-(J3-Pad8)") (class "Default")
      (node (ref "J3") (pin "8") (pintype "passive"))
      (node (ref "U1") (pin "93") (pintype "passive"))
    )
    (net (code "259") (name "Net-(J3-Pad9)") (class "Default")
      (node (ref "J3") (pin "9") (pintype "passive"))
      (node (ref "U1") (pin "92") (pintype "passive"))
    )
    (net (code "260") (name "Net-(J3-Pad10)") (class "Default")
      (node (ref "J3") (pin "10") (pintype "passive"))
      (node (ref "U1") (pin "91") (pintype "passive"))
    )
    (net (code "261") (name "Net-(J3-Pad11)") (class "Default")
      (node (ref "J3") (pin "11") (pintype "passive"))
      (node (ref "U1") (pin "90") (pintype "passive"))
    )
    (net (code "262") (name "Net-(J3-Pad12)") (class "Default")
      (node (ref "J3") (pin "12") (pintype "passive"))
      (node (ref "U1") (pin "89") (pintype "passive"))
    )
    (net (code "263") (name "Net-(J3-Pad13)") (class "Default")
      (node (ref "J3") (pin "13") (pintype "passive"))
      (node (ref "U1") (pin "88") (pintype "passive"))
    )
    (net (code "264") (name "Net-(J3-Pad14)") (class "Default")
      (node (ref "J3") (pin "14") (pintype "passive"))
      (node (ref "U1") (pin "87") (pintype "passive"))
    )
    (net (code "265") (name "Net-(J3-Pad15)") (class "Default")
      (node (ref "J3") (pin "15") (pintype "passive"))
      (node (ref "U1") (pin "86") (pintype "passive"))
    )
    (net (code "266") (name "Net-(J3-Pad16)") (class "Default")
      (node (ref "J3") (pin "16") (pintype "passive"))
      (node (ref "U1") (pin "85") (pintype "passive"))
    )
    (net (code "267") (name "Net-(J3-Pad17)") (class "Default")
      (node (ref "J3") (pin "17") (pintype "passive"))
      (node (ref "U1") (pin "84") (pintype "passive"))
    )
    (net (code "268") (name "Net-(J3-Pad18)") (class "Default")
      (node (ref "J3") (pin "18") (pintype "passive"))
      (node (ref "U1") (pin "83") (pintype "passive"))
    )
    (net (code "269") (name "Net-(J3-Pad19)") (class "Default")
      (node (ref "J3") (pin "19") (pintype "passive"))
      (node (ref "U1") (pin "82") (pintype "passive"))
    )
    (net (code "270") (name "Net-(J3-Pad20)") (class "Default")
      (node (ref "J3") (pin "20") (pintype "passive"))
      (node (ref "U1") (pin "81") (pintype "passive"))
    )
    (net (code "271") (name "Net-(J3-Pad21)") (class "Default")
      (node (ref "J3") (pin "21") (pintype "passive"))
      (node (ref "U1") (pin "80") (pintype "passive"))
    )
    (net (code "272") (name "Net-(J3-Pad22)") (class "Default")
      (node (ref "J3") (pin "22") (pintype "passive"))
      (node (ref "U1") (pin "79") (pintype "passive"))
    )
    (net (code "273") (name "Net-(J3-Pad23)") (class "Default")
      (node (ref "J3") (pin "23") (pintype "passive"))
      (node (ref "U1") (pin "78") (pintype "passive"))
    )
    (net (code "274") (name "Net-(J3-Pad24)") (class "Default")
      (node (ref "J3") (pin "24") (pintype "passive"))
      (node (ref "U1") (pin "77") (pintype "passive"))
    )
    (net (code "275") (name "Net-(J3-Pad25)") (class "Default")
      (node (ref "J3") (pin "25") (pintype "passive"))
      (node (ref "U1") (pin "76") (pintype "passive"))
    )
    (net (code "276") (name "Net-(J3-Pad26)") (class "Default")
      (node (ref "J3") (pin "26") (pintype "passive"))
      (node (ref "U1") (pin "75") (pintype "passive"))
    )
    (net (code "277") (name "Net-(J3-Pad27)") (class "Default")
      (node (ref "J3") (pin "27") (pintype "passive"))
      (node (ref "U1") (pin "74") (pintype "passive"))
    )
    (net (code "278") (name "Net-(J3-Pad28)") (class "Default")
      (node (ref "J3") (pin "28") (pintype "passive"))
      (node (ref "U1") (pin "73") (pintype "passive"))
    )
    (net (code "279") (name "Net-(J3-Pad29)") (class "Default")
      (node (ref "J3") (pin "29") (pintype "passive"))
      (node (ref "U1") (pin "72") (pintype "passive"))
    )
    (net (code "280") (name "Net-(J3-Pad30)") (class "Default")
      (node (ref "J3") (pin "30") (pintype "passive"))
      (node (ref "U1") (pin "71") (pintype "passive"))
    )
    (net (code "281") (name "Net-(J3-Pad31)") (class "Default")
      (node (ref "J3") (pin "31") (pintype "passive"))
      (node (ref "U1") (pin "70") (pintype "passive"))
    )
    (net (code "282") (name "Net-(J3-Pad32)") (class "Default")
      (node (ref "J3") (pin "32") (pintype "passive"))
      (node (ref "U1") (pin "69") (pintype "passive"))
    )
    (net (code "283") (name "Net-(J3-Pad33)") (class "Default")
      (node (ref "J3") (pin "33") (pintype "passive"))
      (node (ref "U1") (pin "68") (pintype "passive"))
    )
    (net (code "284") (name "Net-(J3-Pad34)") (class "Default")
      (node (ref "J3") (pin "34") (pintype "passive"))
      (node (ref "U1") (pin "67") (pintype "passive"))
    )
    (net (code "285") (name "Net-(J3-Pad35)") (class "Default")
      (node (ref "J3") (pin "35") (pintype "passive"))
      (node (ref "U1") (pin "66") (pintype "passive"))
    )
    (net (code "286") (name "Net-(J3-Pad36)") (class "Default")
      (node (ref "J3") (pin "36") (pintype "passive"))
      (node (ref "U1") (pin "65") (pintype "passive"))
    )
    (net (code "287") (name "Net-(J3-Pad37)") (class "Default")
      (node (ref "J3") (pin "37") (pintype "passive"))
      (node (ref "U1") (pin "64") (pintype "passive"))
    )
    (net (code "288") (name "Net-(J3-Pad38)") (class "Default")
      (node (ref "J3") (pin "38") (pintype "passive"))
      (node (ref "U1") (pin "63") (pintype "passive"))
    )
    (net (code "289") (name "Net-(J3-Pad39)") (class "Default")
      (node (ref "J3") (pin "39") (pintype "passive"))
      (node (ref "U1") (pin "62") (pintype "passive"))
    )
    (net (code "290") (name "Net-(J3-Pad40)") (class "Default")
      (node (ref "J3") (pin "40") (pintype "passive"))
      (node (ref "U1") (pin "61") (pintype "passive"))
    )
    (net (code "291") (name "Net-(J3-Pad41)") (class "Default")
      (node (ref "J3") (pin "41") (pintype "passive"))
      (node (ref "U1") (pin "60") (pintype "passive"))
    )
    (net (code "292") (name "Net-(J3-Pad42)") (class "Default")
      (node (ref "J3") (pin "42") (pintype "passive"))
      (node (ref "U1") (pin "59") (pintype "passive"))
    )
    (net (code "293") (name "Net-(J3-Pad43)") (class "Default")
      (node (ref "J3") (pin "43") (pintype "passive"))
      (node (ref "U1") (pin "58") (pintype "passive"))
    )
    (net (code "294") (name "Net-(J3-Pad44)") (class "Default")
      (node (ref "J3") (pin "44") (pintype "passive"))
      (node (ref "U1") (pin "57") (pintype "passive"))
    )
    (net (code "295") (name "Net-(J3-Pad45)") (class "Default")
      (node (ref "J3") (pin "45") (pintype "passive"))
      (node (ref "U1") (pin "56") (pintype "passive"))
    )
    (net (code "296") (name "Net-(J3-Pad46)") (class "Default")
      (node (ref "J3") (pin "46") (pintype "passive"))
      (node (ref "U1") (pin "55") (pintype "passive"))
    )
    (net (code "297") (name "Net-(J3-Pad47)") (class "Default")
      (node (ref "J3") (pin "47") (pintype "passive"))
      (node (ref "U1") (pin "54") (pintype "passive"))
    )
    (net (code "298") (name "Net-(J3-Pad48)") (class "Default")
      (node (ref "J3") (pin "48") (pintype "passive"))
      (node (ref "U1") (pin "53") (pintype "passive"))
    )
    (net (code "299") (name "Net-(J3-Pad49)") (class "Default")
      (node (ref "J3") (pin "49") (pintype "passive"))
      (node (ref "U1") (pin "52") (pintype "passive"))
    )
    (net (code "300") (name "Net-(J3-Pad50)") (class "Default")
      (node (ref "J3") (pin "50") (pintype "passive"))
      (node (ref "U1") (pin "51") (pintype "passive"))
    )
    (net (code "301") (name "Net-(J3-Pad51)") (class "Default")
      (node (ref "J3") (pin "51") (pintype "passive"))
      (node (ref "U1") (pin "150") (pintype "passive"))
    )
    (net (code "302") (name "Net-(J3-Pad52)") (class "Default")
      (node (ref "J3") (pin "52") (pintype "passive"))
      (node (ref "U1") (pin "149") (pintype "passive"))
    )
    (net (code "303") (name "Net-(J3-Pad53)") (class "Default")
      (node (ref "J3") (pin "53") (pintype "passive"))
      (node (ref "U1") (pin "148") (pintype "passive"))
    )
    (net (code "304") (name "Net-(J3-Pad54)") (class "Default")
      (node (ref "J3") (pin "54") (pintype "passive"))
      (node (ref "U1") (pin "147") (pintype "passive"))
    )
    (net (code "305") (name "Net-(J3-Pad55)") (class "Default")
      (node (ref "J3") (pin "55") (pintype "passive"))
      (node (ref "U1") (pin "146") (pintype "passive"))
    )
    (net (code "306") (name "Net-(J3-Pad56)") (class "Default")
      (node (ref "J3") (pin "56") (pintype "passive"))
      (node (ref "U1") (pin "145") (pintype "passive"))
    )
    (net (code "307") (name "Net-(J3-Pad57)") (class "Default")
      (node (ref "J3") (pin "57") (pintype "passive"))
      (node (ref "U1") (pin "144") (pintype "passive"))
    )
    (net (code "308") (name "Net-(J3-Pad58)") (class "Default")
      (node (ref "J3") (pin "58") (pintype "passive"))
      (node (ref "U1") (pin "143") (pintype "passive"))
    )
    (net (code "309") (name "Net-(J3-Pad59)") (class "Default")
      (node (ref "J3") (pin "59") (pintype "passive"))
      (node (ref "U1") (pin "142") (pintype "passive"))
    )
    (net (code "310") (name "Net-(J3-Pad60)") (class "Default")
      (node (ref "J3") (pin "60") (pintype "passive"))
      (node (ref "U1") (pin "141") (pintype "passive"))
    )
    (net (code "311") (name "Net-(J3-Pad61)") (class "Default")
      (node (ref "J3") (pin "61") (pintype "passive"))
      (node (ref "U1") (pin "140") (pintype "passive"))
    )
    (net (code "312") (name "Net-(J3-Pad62)") (class "Default")
      (node (ref "J3") (pin "62") (pintype "passive"))
      (node (ref "U1") (pin "139") (pintype "passive"))
    )
    (net (code "313") (name "Net-(J3-Pad63)") (class "Default")
      (node (ref "J3") (pin "63") (pintype "passive"))
      (node (ref "U1") (pin "138") (pintype "passive"))
    )
    (net (code "314") (name "Net-(J3-Pad64)") (class "Default")
      (node (ref "J3") (pin "64") (pintype "passive"))
      (node (ref "U1") (pin "137") (pintype "passive"))
    )
    (net (code "315") (name "Net-(J3-Pad65)") (class "Default")
      (node (ref "J3") (pin "65") (pintype "passive"))
      (node (ref "U1") (pin "136") (pintype "passive"))
    )
    (net (code "316") (name "Net-(J3-Pad66)") (class "Default")
      (node (ref "J3") (pin "66") (pintype "passive"))
      (node (ref "U1") (pin "135") (pintype "passive"))
    )
    (net (code "317") (name "Net-(J3-Pad67)") (class "Default")
      (node (ref "J3") (pin "67") (pintype "passive"))
      (node (ref "U1") (pin "134") (pintype "passive"))
    )
    (net (code "318") (name "Net-(J3-Pad68)") (class "Default")
      (node (ref "J3") (pin "68") (pintype "passive"))
      (node (ref "U1") (pin "133") (pintype "passive"))
    )
    (net (code "319") (name "Net-(J3-Pad69)") (class "Default")
      (node (ref "J3") (pin "69") (pintype "passive"))
      (node (ref "U1") (pin "132") (pintype "passive"))
    )
    (net (code "320") (name "Net-(J3-Pad70)") (class "Default")
      (node (ref "J3") (pin "70") (pintype "passive"))
      (node (ref "U1") (pin "131") (pintype "passive"))
    )
    (net (code "321") (name "Net-(J3-Pad71)") (class "Default")
      (node (ref "J3") (pin "71") (pintype "passive"))
      (node (ref "U1") (pin "130") (pintype "passive"))
    )
    (net (code "322") (name "Net-(J3-Pad72)") (class "Default")
      (node (ref "J3") (pin "72") (pintype "passive"))
      (node (ref "U1") (pin "129") (pintype "passive"))
    )
    (net (code "323") (name "Net-(J3-Pad73)") (class "Default")
      (node (ref "J3") (pin "73") (pintype "passive"))
      (node (ref "U1") (pin "128") (pintype "passive"))
    )
    (net (code "324") (name "Net-(J3-Pad74)") (class "Default")
      (node (ref "J3") (pin "74") (pintype "passive"))
      (node (ref "U1") (pin "127") (pintype "passive"))
    )
    (net (code "325") (name "Net-(J3-Pad75)") (class "Default")
      (node (ref "J3") (pin "75") (pintype "passive"))
      (node (ref "U1") (pin "126") (pintype "passive"))
    )
    (net (code "326") (name "Net-(J3-Pad76)") (class "Default")
      (node (ref "J3") (pin "76") (pintype "passive"))
      (node (ref "U1") (pin "125") (pintype "passive"))
    )
    (net (code "327") (name "Net-(J3-Pad77)") (class "Default")
      (node (ref "J3") (pin "77") (pintype "passive"))
      (node (ref "U1") (pin "124") (pintype "passive"))
    )
    (net (code "328") (name "Net-(J3-Pad78)") (class "Default")
      (node (ref "J3") (pin "78") (pintype "passive"))
      (node (ref "U1") (pin "123") (pintype "passive"))
    )
    (net (code "329") (name "Net-(J3-Pad79)") (class "Default")
      (node (ref "J3") (pin "79") (pintype "passive"))
      (node (ref "U1") (pin "122") (pintype "passive"))
    )
    (net (code "330") (name "Net-(J3-Pad80)") (class "Default")
      (node (ref "J3") (pin "80") (pintype "passive"))
      (node (ref "U1") (pin "121") (pintype "passive"))
    )
    (net (code "331") (name "Net-(J3-Pad81)") (class "Default")
      (node (ref "J3") (pin "81") (pintype "passive"))
      (node (ref "U1") (pin "120") (pintype "passive"))
    )
    (net (code "332") (name "Net-(J3-Pad82)") (class "Default")
      (node (ref "J3") (pin "82") (pintype "passive"))
      (node (ref "U1") (pin "119") (pintype "passive"))
    )
    (net (code "333") (name "Net-(J3-Pad83)") (class "Default")
      (node (ref "J3") (pin "83") (pintype "passive"))
      (node (ref "U1") (pin "118") (pintype "passive"))
    )
    (net (code "334") (name "Net-(J3-Pad84)") (class "Default")
      (node (ref "J3") (pin "84") (pintype "passive"))
      (node (ref "U1") (pin "117") (pintype "passive"))
    )
    (net (code "335") (name "Net-(J3-Pad85)") (class "Default")
      (node (ref "J3") (pin "85") (pintype "passive"))
      (node (ref "U1") (pin "116") (pintype "passive"))
    )
    (net (code "336") (name "Net-(J3-Pad86)") (class "Default")
      (node (ref "J3") (pin "86") (pintype "passive"))
      (node (ref "U1") (pin "115") (pintype "passive"))
    )
    (net (code "337") (name "Net-(J3-Pad87)") (class "Default")
      (node (ref "J3") (pin "87") (pintype "passive"))
      (node (ref "U1") (pin "114") (pintype "passive"))
    )
    (net (code "338") (name "Net-(J3-Pad88)") (class "Default")
      (node (ref "J3") (pin "88") (pintype "passive"))
      (node (ref "U1") (pin "113") (pintype "passive"))
    )
    (net (code "339") (name "Net-(J3-Pad89)") (class "Default")
      (node (ref "J3") (pin "89") (pintype "passive"))
      (node (ref "U1") (pin "112") (pintype "passive"))
    )
    (net (code "340") (name "Net-(J3-Pad90)") (class "Default")
      (node (ref "J3") (pin "90") (pintype "passive"))
      (node (ref "U1") (pin "111") (pintype "passive"))
    )
    (net (code "341") (name "Net-(J3-Pad91)") (class "Default")
      (node (ref "J3") (pin "91") (pintype "passive"))
      (node (ref "U1") (pin "110") (pintype "passive"))
    )
    (net (code "342") (name "Net-(J3-Pad92)") (class "Default")
      (node (ref "J3") (pin "92") (pintype "passive"))
      (node (ref "U1") (pin "109") (pintype "passive"))
    )
    (net (code "343") (name "Net-(J3-Pad93)") (class "Default")
      (node (ref "J3") (pin "93") (pintype "passive"))
      (node (ref "U1") (pin "108") (pintype "passive"))
    )
    (net (code "344") (name "Net-(J3-Pad94)") (class "Default")
      (node (ref "J3") (pin "94") (pintype "passive"))
      (node (ref "U1") (pin "107") (pintype "passive"))
    )
    (net (code "345") (name "Net-(J3-Pad95)") (class "Default")
      (node (ref "J3") (pin "95") (pintype "passive"))
      (node (ref "U1") (pin "106") (pintype "passive"))
    )
    (net (code "346") (name "Net-(J3-Pad96)") (class "Default")
      (node (ref "J3") (pin "96") (pintype "passive"))
      (node (ref "U1") (pin "105") (pintype "passive"))
    )
    (net (code "347") (name "Net-(J3-Pad97)") (class "Default")
      (node (ref "J3") (pin "97") (pintype "passive"))
      (node (ref "U1") (pin "104") (pintype "passive"))
    )
    (net (code "348") (name "Net-(J3-Pad98)") (class "Default")
      (node (ref "J3") (pin "98") (pintype "passive"))
      (node (ref "U1") (pin "103") (pintype "passive"))
    )
    (net (code "349") (name "Net-(J3-Pad99)") (class "Default")
      (node (ref "J3") (pin "99") (pintype "passive"))
      (node (ref "U1") (pin "102") (pintype "passive"))
    )
    (net (code "350") (name "Net-(J3-Pad100)") (class "Default")
      (node (ref "J3") (pin "100") (pintype "passive"))
      (node (ref "U1") (pin "101") (pintype "passive"))
    )
    (net (code "351") (name "Net-(J3-Pad101)") (class "Default")
      (node (ref "J3") (pin "101") (pintype "passive"))
      (node (ref "U1") (pin "200") (pintype "passive"))
    )
    (net (code "352") (name "Net-(J3-Pad102)") (class "Default")
      (node (ref "J3") (pin "102") (pintype "passive"))
      (node (ref "U1") (pin "199") (pintype "passive"))
    )
    (net (code "353") (name "Net-(J3-Pad103)") (class "Default")
      (node (ref "J3") (pin "103") (pintype "passive"))
      (node (ref "U1") (pin "198") (pintype "passive"))
    )
    (net (code "354") (name "Net-(J3-Pad104)") (class "Default")
      (node (ref "J3") (pin "104") (pintype "passive"))
      (node (ref "U1") (pin "197") (pintype "passive"))
    )
    (net (code "355") (name "Net-(J3-Pad105)") (class "Default")
      (node (ref "J3") (pin "105") (pintype "passive"))
      (node (ref "U1") (pin "196") (pintype "passive"))
    )
    (net (code "356") (name "Net-(J3-Pad106)") (class "Default")
      (node (ref "J3") (pin "106") (pintype "passive"))
      (node (ref "U1") (pin "195") (pintype "passive"))
    )
    (net (code "357") (name "Net-(J3-Pad107)") (class "Default")
      (node (ref "J3") (pin "107") (pintype "passive"))
      (node (ref "U1") (pin "194") (pintype "passive"))
    )
    (net (code "358") (name "Net-(J3-Pad108)") (class "Default")
      (node (ref "J3") (pin "108") (pintype "passive"))
      (node (ref "U1") (pin "193") (pintype "passive"))
    )
    (net (code "359") (name "Net-(J3-Pad109)") (class "Default")
      (node (ref "J3") (pin "109") (pintype "passive"))
      (node (ref "U1") (pin "192") (pintype "passive"))
    )
    (net (code "360") (name "Net-(J3-Pad110)") (class "Default")
      (node (ref "J3") (pin "110") (pintype "passive"))
      (node (ref "U1") (pin "191") (pintype "passive"))
    )
    (net (code "361") (name "Net-(J3-Pad111)") (class "Default")
      (node (ref "J3") (pin "111") (pintype "passive"))
      (node (ref "U1") (pin "190") (pintype "passive"))
    )
    (net (code "362") (name "Net-(J3-Pad112)") (class "Default")
      (node (ref "J3") (pin "112") (pintype "passive"))
      (node (ref "U1") (pin "189") (pintype "passive"))
    )
    (net (code "363") (name "Net-(J3-Pad113)") (class "Default")
      (node (ref "J3") (pin "113") (pintype "passive"))
      (node (ref "U1") (pin "188") (pintype "passive"))
    )
    (net (code "364") (name "Net-(J3-Pad114)") (class "Default")
      (node (ref "J3") (pin "114") (pintype "passive"))
      (node (ref "U1") (pin "187") (pintype "passive"))
    )
    (net (code "365") (name "Net-(J3-Pad115)") (class "Default")
      (node (ref "J3") (pin "115") (pintype "passive"))
      (node (ref "U1") (pin "186") (pintype "passive"))
    )
    (net (code "366") (name "Net-(J3-Pad116)") (class "Default")
      (node (ref "J3") (pin "116") (pintype "passive"))
      (node (ref "U1") (pin "185") (pintype "passive"))
    )
    (net (code "367") (name "Net-(J3-Pad117)") (class "Default")
      (node (ref "J3") (pin "117") (pintype "passive"))
      (node (ref "U1") (pin "184") (pintype "passive"))
    )
    (net (code "368") (name "Net-(J3-Pad118)") (class "Default")
      (node (ref "J3") (pin "118") (pintype "passive"))
      (node (ref "U1") (pin "183") (pintype "passive"))
    )
    (net (code "369") (name "Net-(J3-Pad119)") (class "Default")
      (node (ref "J3") (pin "119") (pintype "passive"))
      (node (ref "U1") (pin "182") (pintype "passive"))
    )
    (net (code "370") (name "Net-(J3-Pad120)") (class "Default")
      (node (ref "J3") (pin "120") (pintype "passive"))
      (node (ref "U1") (pin "181") (pintype "passive"))
    )
    (net (code "371") (name "Net-(J3-Pad121)") (class "Default")
      (node (ref "J3") (pin "121") (pintype "passive"))
      (node (ref "U1") (pin "180") (pintype "passive"))
    )
    (net (code "372") (name "Net-(J3-Pad122)") (class "Default")
      (node (ref "J3") (pin "122") (pintype "passive"))
      (node (ref "U1") (pin "179") (pintype "passive"))
    )
    (net (code "373") (name "Net-(J3-Pad123)") (class "Default")
      (node (ref "J3") (pin "123") (pintype "passive"))
      (node (ref "U1") (pin "178") (pintype "passive"))
    )
    (net (code "374") (name "Net-(J3-Pad124)") (class "Default")
      (node (ref "J3") (pin "124") (pintype "passive"))
      (node (ref "U1") (pin "177") (pintype "passive"))
    )
    (net (code "375") (name "Net-(J3-Pad125)") (class "Default")
      (node (ref "J3") (pin "125") (pintype "passive"))
      (node (ref "U1") (pin "176") (pintype "passive"))
    )
    (net (code "376") (name "Net-(J3-Pad126)") (class "Default")
      (node (ref "J3") (pin "126") (pintype "passive"))
      (node (ref "U1") (pin "175") (pintype "passive"))
    )
    (net (code "377") (name "Net-(J3-Pad127)") (class "Default")
      (node (ref "J3") (pin "127") (pintype "passive"))
      (node (ref "U1") (pin "174") (pintype "passive"))
    )
    (net (code "378") (name "Net-(J3-Pad128)") (class "Default")
      (node (ref "J3") (pin "128") (pintype "passive"))
      (node (ref "U1") (pin "173") (pintype "passive"))
    )
    (net (code "379") (name "Net-(J3-Pad129)") (class "Default")
      (node (ref "J3") (pin "129") (pintype "passive"))
      (node (ref "U1") (pin "172") (pintype "passive"))
    )
    (net (code "380") (name "Net-(J3-Pad130)") (class "Default")
      (node (ref "J3") (pin "130") (pintype "passive"))
      (node (ref "U1") (pin "171") (pintype "passive"))
    )
    (net (code "381") (name "Net-(J3-Pad131)") (class "Default")
      (node (ref "J3") (pin "131") (pintype "passive"))
      (node (ref "U1") (pin "170") (pintype "passive"))
    )
    (net (code "382") (name "Net-(J3-Pad132)") (class "Default")
      (node (ref "J3") (pin "132") (pintype "passive"))
      (node (ref "U1") (pin "169") (pintype "passive"))
    )
    (net (code "383") (name "Net-(J3-Pad133)") (class "Default")
      (node (ref "J3") (pin "133") (pintype "passive"))
      (node (ref "U1") (pin "168") (pintype "passive"))
    )
    (net (code "384") (name "Net-(J3-Pad134)") (class "Default")
      (node (ref "J3") (pin "134") (pintype "passive"))
      (node (ref "U1") (pin "167") (pintype "passive"))
    )
    (net (code "385") (name "Net-(J3-Pad135)") (class "Default")
      (node (ref "J3") (pin "135") (pintype "passive"))
      (node (ref "U1") (pin "166") (pintype "passive"))
    )
    (net (code "386") (name "Net-(J3-Pad136)") (class "Default")
      (node (ref "J3") (pin "136") (pintype "passive"))
      (node (ref "U1") (pin "165") (pintype "passive"))
    )
    (net (code "387") (name "Net-(J3-Pad137)") (class "Default")
      (node (ref "J3") (pin "137") (pintype "passive"))
      (node (ref "U1") (pin "164") (pintype "passive"))
    )
    (net (code "388") (name "Net-(J3-Pad138)") (class "Default")
      (node (ref "J3") (pin "138") (pintype "passive"))
      (node (ref "U1") (pin "163") (pintype "passive"))
    )
    (net (code "389") (name "Net-(J3-Pad139)") (class "Default")
      (node (ref "J3") (pin "139") (pintype "passive"))
      (node (ref "U1") (pin "162") (pintype "passive"))
    )
    (net (code "390") (name "Net-(J3-Pad140)") (class "Default")
      (node (ref "J3") (pin "140") (pintype "passive"))
      (node (ref "U1") (pin "161") (pintype "passive"))
    )
    (net (code "391") (name "Net-(J3-Pad141)") (class "Default")
      (node (ref "J3") (pin "141") (pintype "passive"))
      (node (ref "U1") (pin "160") (pintype "passive"))
    )
    (net (code "392") (name "Net-(J3-Pad142)") (class "Default")
      (node (ref "J3") (pin "142") (pintype "passive"))
      (node (ref "U1") (pin "159") (pintype "passive"))
    )
    (net (code "393") (name "Net-(J3-Pad143)") (class "Default")
      (node (ref "J3") (pin "143") (pintype "passive"))
      (node (ref "U1") (pin "158") (pintype "passive"))
    )
    (net (code "394") (name "Net-(J3-Pad144)") (class "Default")
      (node (ref "J3") (pin "144") (pintype "passive"))
      (node (ref "U1") (pin "157") (pintype "passive"))
    )
    (net (code "395") (name "Net-(J3-Pad145)") (class "Default")
      (node (ref "J3") (pin "145") (pintype "passive"))
      (node (ref "U1") (pin "156") (pintype "passive"))
    )
    (net (code "396") (name "Net-(J3-Pad146)") (class "Default")
      (node (ref "J3") (pin "146") (pintype "passive"))
      (node (ref "U1") (pin "155") (pintype "passive"))
    )
    (net (code "397") (name "Net-(J3-Pad147)") (class "Default")
      (node (ref "J3") (pin "147") (pintype "passive"))
      (node (ref "U1") (pin "154") (pintype "passive"))
    )
    (net (code "398") (name "Net-(J3-Pad148)") (class "Default")
      (node (ref "J3") (pin "148") (pintype "passive"))
      (node (ref "U1") (pin "153") (pintype "passive"))
    )
    (net (code "399") (name "Net-(J3-Pad149)") (class "Default")
      (node (ref "J3") (pin "149") (pintype "passive"))
      (node (ref "U1") (pin "152") (pintype "passive"))
    )
    (net (code "400") (name "Net-(J3-Pad150)") (class "Default")
      (node (ref "J3") (pin "150") (pintype "passive"))
      (node (ref "U1") (pin "151") (pintype "passive"))
    )
  )
)
